# SNES_TST_Sheet1.net
KiCad netlist of a schematic drawn in Altium Designer
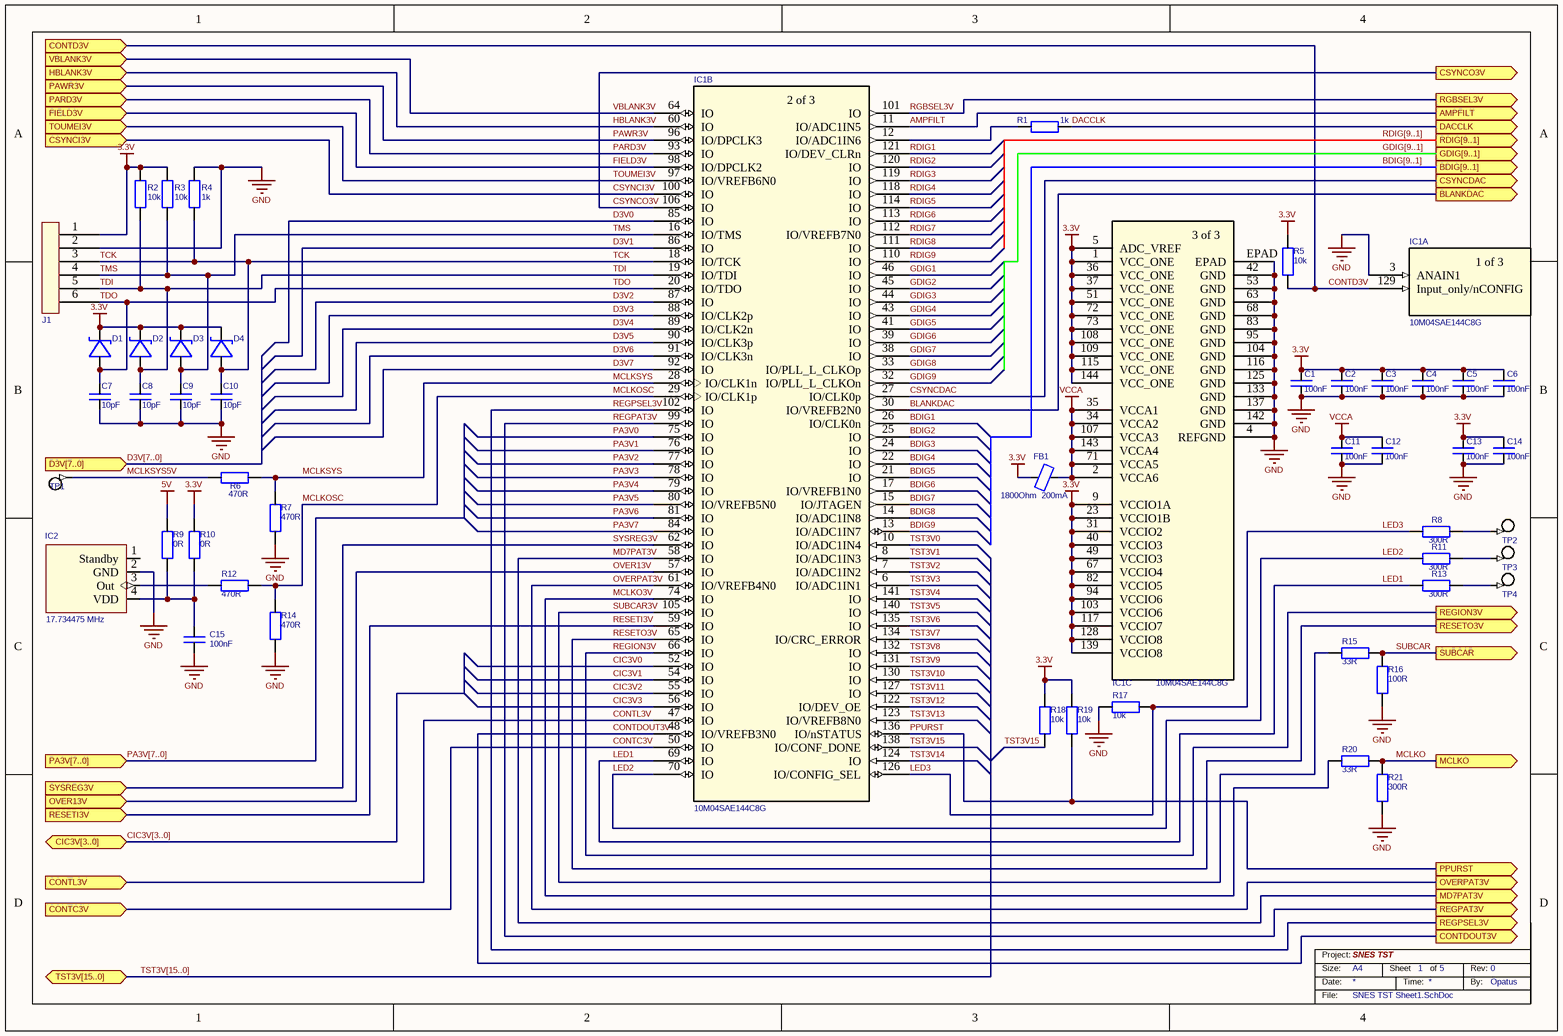
[diagram p0: SNES TST Sheet1.SchDoc]

(export (version "E")
  (design (tool "Eeschema 10.0.6"))
  (components
    (comp (ref "C1")
      (value "100nF")
      (footprint "Cap_0402_Chip")
      (fields (field (name "TOLERANCE") "+-20%"))
      (libsource (lib "PCB") (part "Capacitor"))
    )
    (comp (ref "C2")
      (value "100nF")
      (footprint "Cap_0402_Chip")
      (fields (field (name "TOLERANCE") "+-20%"))
      (libsource (lib "PCB") (part "Capacitor"))
    )
    (comp (ref "C3")
      (value "100nF")
      (footprint "Cap_0402_Chip")
      (fields (field (name "TOLERANCE") "+-20%"))
      (libsource (lib "PCB") (part "Capacitor"))
    )
    (comp (ref "C4")
      (value "100nF")
      (footprint "Cap_0402_Chip")
      (fields (field (name "TOLERANCE") "+-20%"))
      (libsource (lib "PCB") (part "Capacitor"))
    )
    (comp (ref "C5")
      (value "100nF")
      (footprint "Cap_0402_Chip")
      (fields (field (name "TOLERANCE") "+-20%"))
      (libsource (lib "PCB") (part "Capacitor"))
    )
    (comp (ref "C6")
      (value "100nF")
      (footprint "Cap_0402_Chip")
      (fields (field (name "TOLERANCE") "+-20%"))
      (libsource (lib "PCB") (part "Capacitor"))
    )
    (comp (ref "C7")
      (value "10pF")
      (footprint "Cap_0402_Chip")
      (fields (field (name "TOLERANCE") "+-20%"))
      (libsource (lib "PCB") (part "Capacitor"))
    )
    (comp (ref "C8")
      (value "10pF")
      (footprint "Cap_0402_Chip")
      (fields (field (name "TOLERANCE") "+-20%"))
      (libsource (lib "PCB") (part "Capacitor"))
    )
    (comp (ref "C9")
      (value "10pF")
      (footprint "Cap_0402_Chip")
      (fields (field (name "TOLERANCE") "+-20%"))
      (libsource (lib "PCB") (part "Capacitor"))
    )
    (comp (ref "C10")
      (value "10pF")
      (footprint "Cap_0402_Chip")
      (fields (field (name "TOLERANCE") "+-20%"))
      (libsource (lib "PCB") (part "Capacitor"))
    )
    (comp (ref "C11")
      (value "100nF")
      (footprint "Cap_0402_Chip")
      (fields (field (name "TOLERANCE") "+-20%"))
      (libsource (lib "PCB") (part "Capacitor"))
    )
    (comp (ref "C12")
      (value "100nF")
      (footprint "Cap_0402_Chip")
      (fields (field (name "TOLERANCE") "+-20%"))
      (libsource (lib "PCB") (part "Capacitor"))
    )
    (comp (ref "C13")
      (value "100nF")
      (footprint "Cap_0402_Chip")
      (fields (field (name "TOLERANCE") "+-20%"))
      (libsource (lib "PCB") (part "Capacitor"))
    )
    (comp (ref "C14")
      (value "100nF")
      (footprint "Cap_0402_Chip")
      (fields (field (name "TOLERANCE") "+-20%"))
      (libsource (lib "PCB") (part "Capacitor"))
    )
    (comp (ref "C15")
      (value "100nF")
      (footprint "Cap_0402_Chip")
      (fields (field (name "TOLERANCE") "+-20%"))
      (libsource (lib "PCB") (part "Capacitor"))
    )
    (comp (ref "D1")
      (value "Schottky Diode")
      (footprint "SOD323")
      (fields (field (name "MANUFACTURER_PART_NUMBER") "BAT54WS-7-F"))
      (libsource (lib "PCB") (part "Schottky Diode"))
    )
    (comp (ref "D2")
      (value "Schottky Diode")
      (footprint "SOD323")
      (fields (field (name "MANUFACTURER_PART_NUMBER") "BAT54WS-7-F"))
      (libsource (lib "PCB") (part "Schottky Diode"))
    )
    (comp (ref "D3")
      (value "Schottky Diode")
      (footprint "SOD323")
      (fields (field (name "MANUFACTURER_PART_NUMBER") "BAT54WS-7-F"))
      (libsource (lib "PCB") (part "Schottky Diode"))
    )
    (comp (ref "D4")
      (value "Schottky Diode")
      (footprint "SOD323")
      (fields (field (name "MANUFACTURER_PART_NUMBER") "BAT54WS-7-F"))
      (libsource (lib "PCB") (part "Schottky Diode"))
    )
    (comp (ref "FB1")
      (value "1800Ohm  200mA")
      (footprint "Ind_0402_Chip")
      (fields (field (name "MANUFACTURER_PART_NUMBER") "MMZ1005S182ET000"))
      (libsource (lib "PCB") (part "Ferrite Bead"))
    )
    (comp (ref "IC1")
      (value "10M04SAE144C8G")
      (footprint "EQFP-144_A:1P65_")
      (description "No Description Available")
      (fields
        (field (name "MANUFACTURER_PART_NUMBER") "10M08SAE144C8G")
        (field (name "COPYRIGHT") "Copyright (C) 2018 Accelerated Designs. All rights reserved")
      )
      (libsource (lib "PCB") (part "10M08SAE144C8G"))
    )
    (comp (ref "IC2")
      (value "17.734475 MHz")
      (footprint "Quarz 7.5mm")
      (description "Oscillator")
      (fields
        (field (name "FREQUENCY") "17.734475 MHz")
        (field (name "MANUFACTURER_PART_NUMBER") "LFSPXO020648Bulk")
      )
      (libsource (lib "PCB") (part "Oscillator"))
    )
    (comp (ref "J1")
      (value "Conn 6P")
      (footprint "Con6P")
      (description "6 Pole Connector")
      (libsource (lib "PCB") (part "Conn 6P"))
    )
    (comp (ref "R1")
      (value "1k")
      (footprint "Res_0402_Chip")
      (fields (field (name "TOLERANCE") "+-1%"))
      (libsource (lib "") (part "R_2"))
    )
    (comp (ref "R2")
      (value "10k")
      (footprint "Res_0402_Chip")
      (fields (field (name "TOLERANCE") "+-1%"))
      (libsource (lib "") (part "R_1"))
    )
    (comp (ref "R3")
      (value "10k")
      (footprint "Res_0402_Chip")
      (fields (field (name "TOLERANCE") "+-1%"))
      (libsource (lib "") (part "R_1"))
    )
    (comp (ref "R4")
      (value "1k")
      (footprint "Res_0402_Chip")
      (fields (field (name "TOLERANCE") "+-1%"))
      (libsource (lib "") (part "R_3"))
    )
    (comp (ref "R5")
      (value "10k")
      (footprint "Res_0402_Chip")
      (fields (field (name "TOLERANCE") "+-1%"))
      (libsource (lib "") (part "R_1"))
    )
    (comp (ref "R6")
      (value "470R")
      (footprint "Res_0603_Chip")
      (fields (field (name "TOLERANCE") "+-1%"))
      (libsource (lib "PCB") (part "R"))
    )
    (comp (ref "R7")
      (value "470R")
      (footprint "Res_0603_Chip")
      (fields (field (name "TOLERANCE") "+-1%"))
      (libsource (lib "") (part "R_1"))
    )
    (comp (ref "R8")
      (value "300R")
      (footprint "Res_0603_Chip")
      (fields (field (name "TOLERANCE") "+-1%"))
      (libsource (lib "PCB") (part "R"))
    )
    (comp (ref "R9") (value "0R") (footprint "Res_0402_Chip") (libsource (lib "") (part "R_1")))
    (comp (ref "R10") (value "0R") (footprint "Res_0402_Chip") (libsource (lib "") (part "R_1")))
    (comp (ref "R11")
      (value "300R")
      (footprint "Res_0603_Chip")
      (fields (field (name "TOLERANCE") "+-1%"))
      (libsource (lib "PCB") (part "R"))
    )
    (comp (ref "R12")
      (value "470R")
      (footprint "Res_0603_Chip")
      (fields (field (name "TOLERANCE") "+-1%"))
      (libsource (lib "PCB") (part "R"))
    )
    (comp (ref "R13")
      (value "300R")
      (footprint "Res_0603_Chip")
      (fields (field (name "TOLERANCE") "+-1%"))
      (libsource (lib "PCB") (part "R"))
    )
    (comp (ref "R14")
      (value "470R")
      (footprint "Res_0603_Chip")
      (fields (field (name "TOLERANCE") "+-1%"))
      (libsource (lib "") (part "R_1"))
    )
    (comp (ref "R15")
      (value "33R")
      (footprint "Res_0603_Chip")
      (fields (field (name "TOLERANCE") "+-1%"))
      (libsource (lib "PCB") (part "R"))
    )
    (comp (ref "R16")
      (value "100R")
      (footprint "Res_0603_Chip")
      (fields (field (name "TOLERANCE") "+-1%"))
      (libsource (lib "") (part "R_1"))
    )
    (comp (ref "R17")
      (value "10k")
      (footprint "Res_0402_Chip")
      (fields (field (name "TOLERANCE") "+-1%"))
      (libsource (lib "") (part "R_2"))
    )
    (comp (ref "R18")
      (value "10k")
      (footprint "Res_0402_Chip")
      (fields (field (name "TOLERANCE") "+-1%"))
      (libsource (lib "") (part "R_1"))
    )
    (comp (ref "R19")
      (value "10k")
      (footprint "Res_0402_Chip")
      (fields (field (name "TOLERANCE") "+-1%"))
      (libsource (lib "") (part "R_1"))
    )
    (comp (ref "R20")
      (value "33R")
      (footprint "Res_0603_Chip")
      (fields (field (name "TOLERANCE") "+-1%"))
      (libsource (lib "PCB") (part "R"))
    )
    (comp (ref "R21")
      (value "300R")
      (footprint "Res_0603_Chip")
      (fields (field (name "TOLERANCE") "+-1%"))
      (libsource (lib "") (part "R_1"))
    )
    (comp (ref "TP1")
      (value "Pin Connector")
      (footprint "Pin Connector Small")
      (libsource (lib "PCB") (part "Pin Connector"))
    )
    (comp (ref "TP2")
      (value "Pin Connector")
      (footprint "Pin Connector Small")
      (libsource (lib "PCB") (part "Pin Connector"))
    )
    (comp (ref "TP3")
      (value "Pin Connector")
      (footprint "Pin Connector Small")
      (libsource (lib "PCB") (part "Pin Connector"))
    )
    (comp (ref "TP4")
      (value "Pin Connector")
      (footprint "Pin Connector Small")
      (libsource (lib "PCB") (part "Pin Connector"))
    )
  )
  (nets
    (net (code "1") (name "/AMPFILT") (class "Default")
      (node (ref "IC1") (pin "11") (pinfunction "IO/ADC1IN5_11") (pintype "output"))
    )
    (net (code "2") (name "/BDIG1") (class "Default")
      (node (ref "IC1") (pin "26") (pinfunction "IO/CLK0n_26") (pintype "output"))
    )
    (net (code "3") (name "/BDIG2") (class "Default")
      (node (ref "IC1") (pin "25") (pinfunction "IO_25") (pintype "output"))
    )
    (net (code "4") (name "/BDIG3") (class "Default")
      (node (ref "IC1") (pin "24") (pinfunction "IO_24") (pintype "output"))
    )
    (net (code "5") (name "/BDIG4") (class "Default")
      (node (ref "IC1") (pin "22") (pinfunction "IO_22") (pintype "output"))
    )
    (net (code "6") (name "/BDIG5") (class "Default")
      (node (ref "IC1") (pin "21") (pinfunction "IO_21") (pintype "output"))
    )
    (net (code "7") (name "/BDIG6") (class "Default")
      (node (ref "IC1") (pin "17") (pinfunction "IO/VREFB1N0_17") (pintype "output"))
    )
    (net (code "8") (name "/BDIG7") (class "Default")
      (node (ref "IC1") (pin "15") (pinfunction "IO/JTAGEN_15") (pintype "output"))
    )
    (net (code "9") (name "/BDIG8") (class "Default")
      (node (ref "IC1") (pin "14") (pinfunction "IO/ADC1IN8_14") (pintype "output"))
    )
    (net (code "10") (name "/BDIG9") (class "Default")
      (node (ref "IC1") (pin "13") (pinfunction "IO/ADC1IN7_13") (pintype "bidirectional"))
    )
    (net (code "12") (name "/BLANKDAC") (class "Default")
      (node (ref "IC1") (pin "30") (pinfunction "IO/VREFB2N0_30") (pintype "output"))
    )
    (net (code "13") (name "/CIC3V0") (class "Default")
      (node (ref "IC1") (pin "52") (pinfunction "IO_52") (pintype "bidirectional"))
    )
    (net (code "14") (name "/CIC3V1") (class "Default")
      (node (ref "IC1") (pin "54") (pinfunction "IO_54") (pintype "bidirectional"))
    )
    (net (code "15") (name "/CIC3V2") (class "Default")
      (node (ref "IC1") (pin "55") (pinfunction "IO_55") (pintype "bidirectional"))
    )
    (net (code "16") (name "/CIC3V3") (class "Default")
      (node (ref "IC1") (pin "56") (pinfunction "IO_56") (pintype "bidirectional"))
    )
    (net (code "18") (name "/CONTC3V") (class "Default")
      (node (ref "IC1") (pin "50") (pinfunction "IO_50") (pintype "bidirectional"))
    )
    (net (code "19") (name "/CONTD3V") (class "Default")
      (node (ref "IC1") (pin "129") (pinfunction "Input_only/nCONFIG_129") (pintype "input"))
      (node (ref "R5") (pin "2") (pintype "passive"))
    )
    (net (code "20") (name "/CONTDOUT3V") (class "Default")
      (node (ref "IC1") (pin "48") (pinfunction "IO/VREFB3N0_48") (pintype "bidirectional"))
    )
    (net (code "21") (name "/CONTL3V") (class "Default")
      (node (ref "IC1") (pin "47") (pinfunction "IO_47") (pintype "bidirectional"))
    )
    (net (code "22") (name "/CSYNCDAC") (class "Default")
      (node (ref "IC1") (pin "27") (pinfunction "IO/CLK0p_27") (pintype "output"))
    )
    (net (code "23") (name "/CSYNCI3V") (class "Default")
      (node (ref "IC1") (pin "100") (pinfunction "IO_100") (pintype "bidirectional"))
    )
    (net (code "24") (name "/CSYNCO3V") (class "Default")
      (node (ref "IC1") (pin "106") (pinfunction "IO_106") (pintype "bidirectional"))
    )
    (net (code "25") (name "/D3V0") (class "Default")
      (node (ref "IC1") (pin "85") (pinfunction "IO_85") (pintype "bidirectional"))
    )
    (net (code "26") (name "/D3V1") (class "Default")
      (node (ref "IC1") (pin "86") (pinfunction "IO_86") (pintype "bidirectional"))
    )
    (net (code "27") (name "/D3V2") (class "Default")
      (node (ref "IC1") (pin "87") (pinfunction "IO_87") (pintype "bidirectional"))
    )
    (net (code "28") (name "/D3V3") (class "Default")
      (node (ref "IC1") (pin "88") (pinfunction "IO/CLK2p_88") (pintype "bidirectional"))
    )
    (net (code "29") (name "/D3V4") (class "Default")
      (node (ref "IC1") (pin "89") (pinfunction "IO/CLK2n_89") (pintype "bidirectional"))
    )
    (net (code "30") (name "/D3V5") (class "Default")
      (node (ref "IC1") (pin "90") (pinfunction "IO/CLK3p_90") (pintype "bidirectional"))
    )
    (net (code "31") (name "/D3V6") (class "Default")
      (node (ref "IC1") (pin "91") (pinfunction "IO/CLK3n_91") (pintype "bidirectional"))
    )
    (net (code "32") (name "/D3V7") (class "Default")
      (node (ref "IC1") (pin "92") (pinfunction "IO_92") (pintype "bidirectional"))
    )
    (net (code "34") (name "/DACCLK") (class "Default") (node (ref "R1") (pin "2") (pintype "passive")))
    (net (code "35") (name "/FIELD3V") (class "Default")
      (node (ref "IC1") (pin "98") (pinfunction "IO/DPCLK2_98") (pintype "bidirectional"))
    )
    (net (code "36") (name "/GDIG1") (class "Default")
      (node (ref "IC1") (pin "46") (pinfunction "IO_46") (pintype "output"))
    )
    (net (code "37") (name "/GDIG2") (class "Default")
      (node (ref "IC1") (pin "45") (pinfunction "IO_45") (pintype "output"))
    )
    (net (code "38") (name "/GDIG3") (class "Default")
      (node (ref "IC1") (pin "44") (pinfunction "IO_44") (pintype "output"))
    )
    (net (code "39") (name "/GDIG4") (class "Default")
      (node (ref "IC1") (pin "43") (pinfunction "IO_43") (pintype "output"))
    )
    (net (code "40") (name "/GDIG5") (class "Default")
      (node (ref "IC1") (pin "41") (pinfunction "IO_41") (pintype "output"))
    )
    (net (code "41") (name "/GDIG6") (class "Default")
      (node (ref "IC1") (pin "39") (pinfunction "IO_39") (pintype "output"))
    )
    (net (code "42") (name "/GDIG7") (class "Default")
      (node (ref "IC1") (pin "38") (pinfunction "IO_38") (pintype "output"))
    )
    (net (code "43") (name "/GDIG8") (class "Default")
      (node (ref "IC1") (pin "33") (pinfunction "IO/PLL_L_CLKOp_33") (pintype "output"))
    )
    (net (code "44") (name "/GDIG9") (class "Default")
      (node (ref "IC1") (pin "32") (pinfunction "IO/PLL_L_CLKOn_32") (pintype "output"))
    )
    (net (code "46") (name "/HBLANK3V") (class "Default")
      (node (ref "IC1") (pin "60") (pinfunction "IO_60") (pintype "bidirectional"))
    )
    (net (code "47") (name "/LED1") (class "Default")
      (node (ref "IC1") (pin "69") (pinfunction "IO_69") (pintype "bidirectional"))
      (node (ref "R13") (pin "2") (pintype "passive"))
    )
    (net (code "48") (name "/LED2") (class "Default")
      (node (ref "IC1") (pin "70") (pinfunction "IO_70") (pintype "bidirectional"))
      (node (ref "R11") (pin "2") (pintype "passive"))
    )
    (net (code "49") (name "/LED3") (class "Default")
      (node (ref "IC1") (pin "126") (pinfunction "IO/CONFIG_SEL_126") (pintype "bidirectional"))
      (node (ref "R17") (pin "2") (pintype "passive"))
      (node (ref "R8") (pin "2") (pintype "passive"))
    )
    (net (code "50") (name "/MCLKO") (class "Default")
      (node (ref "R20") (pin "1") (pintype "passive"))
      (node (ref "R21") (pin "1") (pintype "passive"))
    )
    (net (code "51") (name "/MCLKO3V") (class "Default")
      (node (ref "IC1") (pin "74") (pinfunction "IO_74") (pintype "bidirectional"))
      (node (ref "R20") (pin "2") (pintype "passive"))
    )
    (net (code "52") (name "/MCLKOSC") (class "Default")
      (node (ref "IC1") (pin "29") (pinfunction "IO/CLK1p_29") (pintype "bidirectional"))
      (node (ref "R12") (pin "1") (pintype "passive"))
      (node (ref "R14") (pin "1") (pintype "passive"))
    )
    (net (code "53") (name "/MCLKSYS") (class "Default")
      (node (ref "IC1") (pin "28") (pinfunction "IO/CLK1n_28") (pintype "bidirectional"))
      (node (ref "R6") (pin "1") (pintype "passive"))
      (node (ref "R7") (pin "1") (pintype "passive"))
    )
    (net (code "54") (name "/MCLKSYS5V") (class "Default")
      (node (ref "R6") (pin "2") (pintype "passive"))
      (node (ref "TP1") (pin "1") (pinfunction "0_1") (pintype "output"))
    )
    (net (code "55") (name "/MD7PAT3V") (class "Default")
      (node (ref "IC1") (pin "58") (pinfunction "IO_58") (pintype "bidirectional"))
    )
    (net (code "56") (name "/OVER13V") (class "Default")
      (node (ref "IC1") (pin "57") (pinfunction "IO_57") (pintype "bidirectional"))
    )
    (net (code "57") (name "/OVERPAT3V") (class "Default")
      (node (ref "IC1") (pin "61") (pinfunction "IO/VREFB4N0_61") (pintype "bidirectional"))
    )
    (net (code "58") (name "/PA3V0") (class "Default")
      (node (ref "IC1") (pin "75") (pinfunction "IO_75") (pintype "bidirectional"))
    )
    (net (code "59") (name "/PA3V1") (class "Default")
      (node (ref "IC1") (pin "76") (pinfunction "IO_76") (pintype "bidirectional"))
    )
    (net (code "60") (name "/PA3V2") (class "Default")
      (node (ref "IC1") (pin "77") (pinfunction "IO_77") (pintype "bidirectional"))
    )
    (net (code "61") (name "/PA3V3") (class "Default")
      (node (ref "IC1") (pin "78") (pinfunction "IO_78") (pintype "bidirectional"))
    )
    (net (code "62") (name "/PA3V4") (class "Default")
      (node (ref "IC1") (pin "79") (pinfunction "IO_79") (pintype "bidirectional"))
    )
    (net (code "63") (name "/PA3V5") (class "Default")
      (node (ref "IC1") (pin "80") (pinfunction "IO/VREFB5N0_80") (pintype "bidirectional"))
    )
    (net (code "64") (name "/PA3V6") (class "Default")
      (node (ref "IC1") (pin "81") (pinfunction "IO_81") (pintype "bidirectional"))
    )
    (net (code "65") (name "/PA3V7") (class "Default")
      (node (ref "IC1") (pin "84") (pinfunction "IO_84") (pintype "bidirectional"))
    )
    (net (code "67") (name "/PARD3V") (class "Default")
      (node (ref "IC1") (pin "93") (pinfunction "IO_93") (pintype "bidirectional"))
    )
    (net (code "68") (name "/PAWR3V") (class "Default")
      (node (ref "IC1") (pin "96") (pinfunction "IO/DPCLK3_96") (pintype "bidirectional"))
    )
    (net (code "69") (name "/PPURST") (class "Default")
      (node (ref "IC1") (pin "136") (pinfunction "IO/nSTATUS_136") (pintype "bidirectional"))
      (node (ref "R19") (pin "2") (pintype "passive"))
    )
    (net (code "70") (name "/RDIG1") (class "Default")
      (node (ref "IC1") (pin "121") (pinfunction "IO/DEV_CLRn_121") (pintype "output"))
    )
    (net (code "71") (name "/RDIG2") (class "Default")
      (node (ref "IC1") (pin "120") (pinfunction "IO_120") (pintype "output"))
    )
    (net (code "72") (name "/RDIG3") (class "Default")
      (node (ref "IC1") (pin "119") (pinfunction "IO_119") (pintype "output"))
    )
    (net (code "73") (name "/RDIG4") (class "Default")
      (node (ref "IC1") (pin "118") (pinfunction "IO_118") (pintype "output"))
    )
    (net (code "74") (name "/RDIG5") (class "Default")
      (node (ref "IC1") (pin "114") (pinfunction "IO_114") (pintype "output"))
    )
    (net (code "75") (name "/RDIG6") (class "Default")
      (node (ref "IC1") (pin "113") (pinfunction "IO_113") (pintype "output"))
    )
    (net (code "76") (name "/RDIG7") (class "Default")
      (node (ref "IC1") (pin "112") (pinfunction "IO/VREFB7N0_112") (pintype "output"))
    )
    (net (code "77") (name "/RDIG8") (class "Default")
      (node (ref "IC1") (pin "111") (pinfunction "IO_111") (pintype "output"))
    )
    (net (code "78") (name "/RDIG9") (class "Default")
      (node (ref "IC1") (pin "110") (pinfunction "IO_110") (pintype "output"))
    )
    (net (code "80") (name "/REGION3V") (class "Default")
      (node (ref "IC1") (pin "66") (pinfunction "IO_66") (pintype "bidirectional"))
    )
    (net (code "81") (name "/REGPAT3V") (class "Default")
      (node (ref "IC1") (pin "99") (pinfunction "IO_99") (pintype "bidirectional"))
    )
    (net (code "82") (name "/REGPSEL3V") (class "Default")
      (node (ref "IC1") (pin "102") (pinfunction "IO_102") (pintype "bidirectional"))
    )
    (net (code "83") (name "/RESETI3V") (class "Default")
      (node (ref "IC1") (pin "59") (pinfunction "IO_59") (pintype "bidirectional"))
    )
    (net (code "84") (name "/RESETO3V") (class "Default")
      (node (ref "IC1") (pin "65") (pinfunction "IO_65") (pintype "bidirectional"))
    )
    (net (code "85") (name "/RGBSEL3V") (class "Default")
      (node (ref "IC1") (pin "101") (pinfunction "IO_101") (pintype "output"))
    )
    (net (code "86") (name "/SUBCAR") (class "Default")
      (node (ref "R15") (pin "1") (pintype "passive"))
      (node (ref "R16") (pin "1") (pintype "passive"))
    )
    (net (code "87") (name "/SUBCAR3V") (class "Default")
      (node (ref "IC1") (pin "105") (pinfunction "IO_105") (pintype "bidirectional"))
      (node (ref "R15") (pin "2") (pintype "passive"))
    )
    (net (code "88") (name "/SYSREG3V") (class "Default")
      (node (ref "IC1") (pin "62") (pinfunction "IO_62") (pintype "bidirectional"))
    )
    (net (code "89") (name "/TCK") (class "Default")
      (node (ref "C10") (pin "1") (pintype "passive"))
      (node (ref "D4") (pin "2") (pinfunction "A_2") (pintype "passive"))
      (node (ref "IC1") (pin "18") (pinfunction "IO/TCK_18") (pintype "bidirectional"))
      (node (ref "J1") (pin "3") (pintype "passive"))
      (node (ref "R4") (pin "1") (pintype "passive"))
    )
    (net (code "90") (name "/TDI") (class "Default")
      (node (ref "C8") (pin "1") (pintype "passive"))
      (node (ref "D2") (pin "2") (pinfunction "A_2") (pintype "passive"))
      (node (ref "IC1") (pin "19") (pinfunction "IO/TDI_19") (pintype "bidirectional"))
      (node (ref "J1") (pin "5") (pintype "passive"))
      (node (ref "R2") (pin "2") (pintype "passive"))
    )
    (net (code "91") (name "/TDO") (class "Default")
      (node (ref "C7") (pin "1") (pintype "passive"))
      (node (ref "D1") (pin "2") (pinfunction "A_2") (pintype "passive"))
      (node (ref "IC1") (pin "20") (pinfunction "IO/TDO_20") (pintype "bidirectional"))
      (node (ref "J1") (pin "6") (pintype "passive"))
    )
    (net (code "92") (name "/TMS") (class "Default")
      (node (ref "C9") (pin "1") (pintype "passive"))
      (node (ref "D3") (pin "2") (pinfunction "A_2") (pintype "passive"))
      (node (ref "IC1") (pin "16") (pinfunction "IO/TMS_16") (pintype "bidirectional"))
      (node (ref "J1") (pin "4") (pintype "passive"))
      (node (ref "R3") (pin "2") (pintype "passive"))
    )
    (net (code "93") (name "/TOUMEI3V") (class "Default")
      (node (ref "IC1") (pin "97") (pinfunction "IO/VREFB6N0_97") (pintype "bidirectional"))
    )
    (net (code "94") (name "/TST3V0") (class "Default")
      (node (ref "IC1") (pin "10") (pinfunction "IO/ADC1IN4_10") (pintype "input"))
    )
    (net (code "95") (name "/TST3V1") (class "Default")
      (node (ref "IC1") (pin "8") (pinfunction "IO/ADC1IN3_8") (pintype "input"))
    )
    (net (code "96") (name "/TST3V2") (class "Default")
      (node (ref "IC1") (pin "7") (pinfunction "IO/ADC1IN2_7") (pintype "input"))
    )
    (net (code "97") (name "/TST3V3") (class "Default")
      (node (ref "IC1") (pin "6") (pinfunction "IO/ADC1IN1_6") (pintype "input"))
    )
    (net (code "98") (name "/TST3V4") (class "Default")
      (node (ref "IC1") (pin "141") (pinfunction "IO_141") (pintype "input"))
    )
    (net (code "99") (name "/TST3V5") (class "Default")
      (node (ref "IC1") (pin "140") (pinfunction "IO_140") (pintype "input"))
    )
    (net (code "100") (name "/TST3V6") (class "Default")
      (node (ref "IC1") (pin "135") (pinfunction "IO_135") (pintype "input"))
    )
    (net (code "101") (name "/TST3V7") (class "Default")
      (node (ref "IC1") (pin "134") (pinfunction "IO/CRC_ERROR_134") (pintype "input"))
    )
    (net (code "102") (name "/TST3V8") (class "Default")
      (node (ref "IC1") (pin "132") (pinfunction "IO_132") (pintype "input"))
    )
    (net (code "103") (name "/TST3V9") (class "Default")
      (node (ref "IC1") (pin "131") (pinfunction "IO_131") (pintype "input"))
    )
    (net (code "104") (name "/TST3V10") (class "Default")
      (node (ref "IC1") (pin "130") (pinfunction "IO_130") (pintype "input"))
    )
    (net (code "105") (name "/TST3V11") (class "Default")
      (node (ref "IC1") (pin "127") (pinfunction "IO_127") (pintype "input"))
    )
    (net (code "106") (name "/TST3V12") (class "Default")
      (node (ref "IC1") (pin "122") (pinfunction "IO/DEV_OE_122") (pintype "input"))
    )
    (net (code "107") (name "/TST3V13") (class "Default")
      (node (ref "IC1") (pin "123") (pinfunction "IO/VREFB8N0_123") (pintype "input"))
    )
    (net (code "108") (name "/TST3V14") (class "Default")
      (node (ref "IC1") (pin "124") (pinfunction "IO_124") (pintype "input"))
    )
    (net (code "109") (name "/TST3V15") (class "Default")
      (node (ref "IC1") (pin "138") (pinfunction "IO/CONF_DONE_138") (pintype "bidirectional"))
      (node (ref "R18") (pin "2") (pintype "passive"))
    )
    (net (code "111") (name "/VBLANK3V") (class "Default")
      (node (ref "IC1") (pin "64") (pinfunction "IO_64") (pintype "bidirectional"))
    )
    (net (code "112") (name "3.3V") (class "Default")
      (node (ref "C1") (pin "1") (pintype "passive"))
      (node (ref "C13") (pin "1") (pintype "passive"))
      (node (ref "C14") (pin "1") (pintype "passive"))
      (node (ref "C2") (pin "1") (pintype "passive"))
      (node (ref "C3") (pin "1") (pintype "passive"))
      (node (ref "C4") (pin "1") (pintype "passive"))
      (node (ref "C5") (pin "1") (pintype "passive"))
      (node (ref "C6") (pin "1") (pintype "passive"))
      (node (ref "D1") (pin "1") (pinfunction "K_1") (pintype "passive"))
      (node (ref "D2") (pin "1") (pinfunction "K_1") (pintype "passive"))
      (node (ref "D3") (pin "1") (pinfunction "K_1") (pintype "passive"))
      (node (ref "D4") (pin "1") (pinfunction "K_1") (pintype "passive"))
      (node (ref "FB1") (pin "1") (pintype "passive"))
      (node (ref "IC1") (pin "1") (pinfunction "VCC_ONE_1") (pintype "power_in"))
      (node (ref "IC1") (pin "103") (pinfunction "VCCIO6_103") (pintype "power_in"))
      (node (ref "IC1") (pin "108") (pinfunction "VCC_ONE_108") (pintype "power_in"))
      (node (ref "IC1") (pin "109") (pinfunction "VCC_ONE_109") (pintype "power_in"))
      (node (ref "IC1") (pin "115") (pinfunction "VCC_ONE_115") (pintype "power_in"))
      (node (ref "IC1") (pin "117") (pinfunction "VCCIO7_117") (pintype "power_in"))
      (node (ref "IC1") (pin "128") (pinfunction "VCCIO8_128") (pintype "power_in"))
      (node (ref "IC1") (pin "139") (pinfunction "VCCIO8_139") (pintype "power_in"))
      (node (ref "IC1") (pin "144") (pinfunction "VCC_ONE_144") (pintype "power_in"))
      (node (ref "IC1") (pin "23") (pinfunction "VCCIO1B_23") (pintype "power_in"))
      (node (ref "IC1") (pin "31") (pinfunction "VCCIO2_31") (pintype "power_in"))
      (node (ref "IC1") (pin "36") (pinfunction "VCC_ONE_36") (pintype "power_in"))
      (node (ref "IC1") (pin "37") (pinfunction "VCC_ONE_37") (pintype "power_in"))
      (node (ref "IC1") (pin "40") (pinfunction "VCCIO3_40") (pintype "power_in"))
      (node (ref "IC1") (pin "49") (pinfunction "VCCIO3_49") (pintype "power_in"))
      (node (ref "IC1") (pin "5") (pinfunction "ADC_VREF_5") (pintype "power_in"))
      (node (ref "IC1") (pin "51") (pinfunction "VCC_ONE_51") (pintype "power_in"))
      (node (ref "IC1") (pin "67") (pinfunction "VCCIO4_67") (pintype "power_in"))
      (node (ref "IC1") (pin "72") (pinfunction "VCC_ONE_72") (pintype "power_in"))
      (node (ref "IC1") (pin "73") (pinfunction "VCC_ONE_73") (pintype "power_in"))
      (node (ref "IC1") (pin "82") (pinfunction "VCCIO5_82") (pintype "power_in"))
      (node (ref "IC1") (pin "9") (pinfunction "VCCIO1A_9") (pintype "power_in"))
      (node (ref "IC1") (pin "94") (pinfunction "VCCIO6_94") (pintype "power_in"))
      (node (ref "J1") (pin "1") (pintype "passive"))
      (node (ref "R10") (pin "1") (pintype "passive"))
      (node (ref "R18") (pin "1") (pintype "passive"))
      (node (ref "R19") (pin "1") (pintype "passive"))
      (node (ref "R2") (pin "1") (pintype "passive"))
      (node (ref "R3") (pin "1") (pintype "passive"))
      (node (ref "R5") (pin "1") (pintype "passive"))
    )
    (net (code "113") (name "5V") (class "Default") (node (ref "R9") (pin "1") (pintype "passive")))
    (net (code "114") (name "GND") (class "Default")
      (node (ref "C1") (pin "2") (pintype "passive"))
      (node (ref "C10") (pin "2") (pintype "passive"))
      (node (ref "C11") (pin "2") (pintype "passive"))
      (node (ref "C12") (pin "2") (pintype "passive"))
      (node (ref "C13") (pin "2") (pintype "passive"))
      (node (ref "C14") (pin "2") (pintype "passive"))
      (node (ref "C15") (pin "2") (pintype "passive"))
      (node (ref "C2") (pin "2") (pintype "passive"))
      (node (ref "C3") (pin "2") (pintype "passive"))
      (node (ref "C4") (pin "2") (pintype "passive"))
      (node (ref "C5") (pin "2") (pintype "passive"))
      (node (ref "C6") (pin "2") (pintype "passive"))
      (node (ref "C7") (pin "2") (pintype "passive"))
      (node (ref "C8") (pin "2") (pintype "passive"))
      (node (ref "C9") (pin "2") (pintype "passive"))
      (node (ref "IC1") (pin "104") (pinfunction "GND_104") (pintype "power_in"))
      (node (ref "IC1") (pin "116") (pinfunction "GND_116") (pintype "power_in"))
      (node (ref "IC1") (pin "125") (pinfunction "GND_125") (pintype "power_in"))
      (node (ref "IC1") (pin "133") (pinfunction "GND_133") (pintype "power_in"))
      (node (ref "IC1") (pin "137") (pinfunction "GND_137") (pintype "power_in"))
      (node (ref "IC1") (pin "142") (pinfunction "GND_142") (pintype "power_in"))
      (node (ref "IC1") (pin "3") (pinfunction "ANAIN1_3") (pintype "input"))
      (node (ref "IC1") (pin "4") (pinfunction "REFGND_4") (pintype "power_in"))
      (node (ref "IC1") (pin "42") (pinfunction "GND_42") (pintype "power_in"))
      (node (ref "IC1") (pin "53") (pinfunction "GND_53") (pintype "power_in"))
      (node (ref "IC1") (pin "63") (pinfunction "GND_63") (pintype "power_in"))
      (node (ref "IC1") (pin "68") (pinfunction "GND_68") (pintype "power_in"))
      (node (ref "IC1") (pin "83") (pinfunction "GND_83") (pintype "power_in"))
      (node (ref "IC1") (pin "95") (pinfunction "GND_95") (pintype "power_in"))
      (node (ref "IC1") (pin "EPAD") (pinfunction "EPAD_EPAD") (pintype "power_in"))
      (node (ref "IC2") (pin "2") (pinfunction "GND_2") (pintype "power_in"))
      (node (ref "J1") (pin "2") (pintype "passive"))
      (node (ref "R14") (pin "2") (pintype "passive"))
      (node (ref "R16") (pin "2") (pintype "passive"))
      (node (ref "R17") (pin "1") (pintype "passive"))
      (node (ref "R21") (pin "2") (pintype "passive"))
      (node (ref "R4") (pin "2") (pintype "passive"))
      (node (ref "R7") (pin "2") (pintype "passive"))
    )
    (net (code "115") (name "Net-(IC1B-IO{slash}ADC1IN6)") (class "Default")
      (node (ref "IC1") (pin "12") (pinfunction "IO/ADC1IN6_12") (pintype "output"))
      (node (ref "R1") (pin "1") (pintype "passive"))
    )
    (net (code "116") (name "Net-(IC2-Out)") (class "Default")
      (node (ref "IC2") (pin "3") (pinfunction "Out_3") (pintype "output"))
      (node (ref "R12") (pin "2") (pintype "passive"))
    )
    (net (code "117") (name "Net-(IC2-VDD)") (class "Default")
      (node (ref "C15") (pin "1") (pintype "passive"))
      (node (ref "IC2") (pin "4") (pinfunction "VDD_4") (pintype "power_in"))
      (node (ref "R10") (pin "2") (pintype "passive"))
      (node (ref "R9") (pin "2") (pintype "passive"))
    )
    (net (code "118") (name "Net-(TP2-0)") (class "Default")
      (node (ref "R8") (pin "1") (pintype "passive"))
      (node (ref "TP2") (pin "1") (pinfunction "0_1") (pintype "output"))
    )
    (net (code "119") (name "Net-(TP3-0)") (class "Default")
      (node (ref "R11") (pin "1") (pintype "passive"))
      (node (ref "TP3") (pin "1") (pinfunction "0_1") (pintype "output"))
    )
    (net (code "120") (name "Net-(TP4-0)") (class "Default")
      (node (ref "R13") (pin "1") (pintype "passive"))
      (node (ref "TP4") (pin "1") (pinfunction "0_1") (pintype "output"))
    )
    (net (code "121") (name "VCCA") (class "Default")
      (node (ref "C11") (pin "1") (pintype "passive"))
      (node (ref "C12") (pin "1") (pintype "passive"))
      (node (ref "FB1") (pin "2") (pintype "passive"))
      (node (ref "IC1") (pin "107") (pinfunction "VCCA3_107") (pintype "power_in"))
      (node (ref "IC1") (pin "143") (pinfunction "VCCA4_143") (pintype "power_in"))
      (node (ref "IC1") (pin "2") (pinfunction "VCCA6_2") (pintype "power_in"))
      (node (ref "IC1") (pin "34") (pinfunction "VCCA2_34") (pintype "power_in"))
      (node (ref "IC1") (pin "35") (pinfunction "VCCA1_35") (pintype "power_in"))
      (node (ref "IC1") (pin "71") (pinfunction "VCCA5_71") (pintype "power_in"))
    )
    (net (code "122") (name "unconnected-(IC2-Standby-Pad1)") (class "Default")
      (node (ref "IC2") (pin "1") (pinfunction "Standby_1") (pintype "passive"))
    )
  )
)
